# Arduino_FPGA_Design.net
KiCad netlist of a schematic drawn in Altium Designer
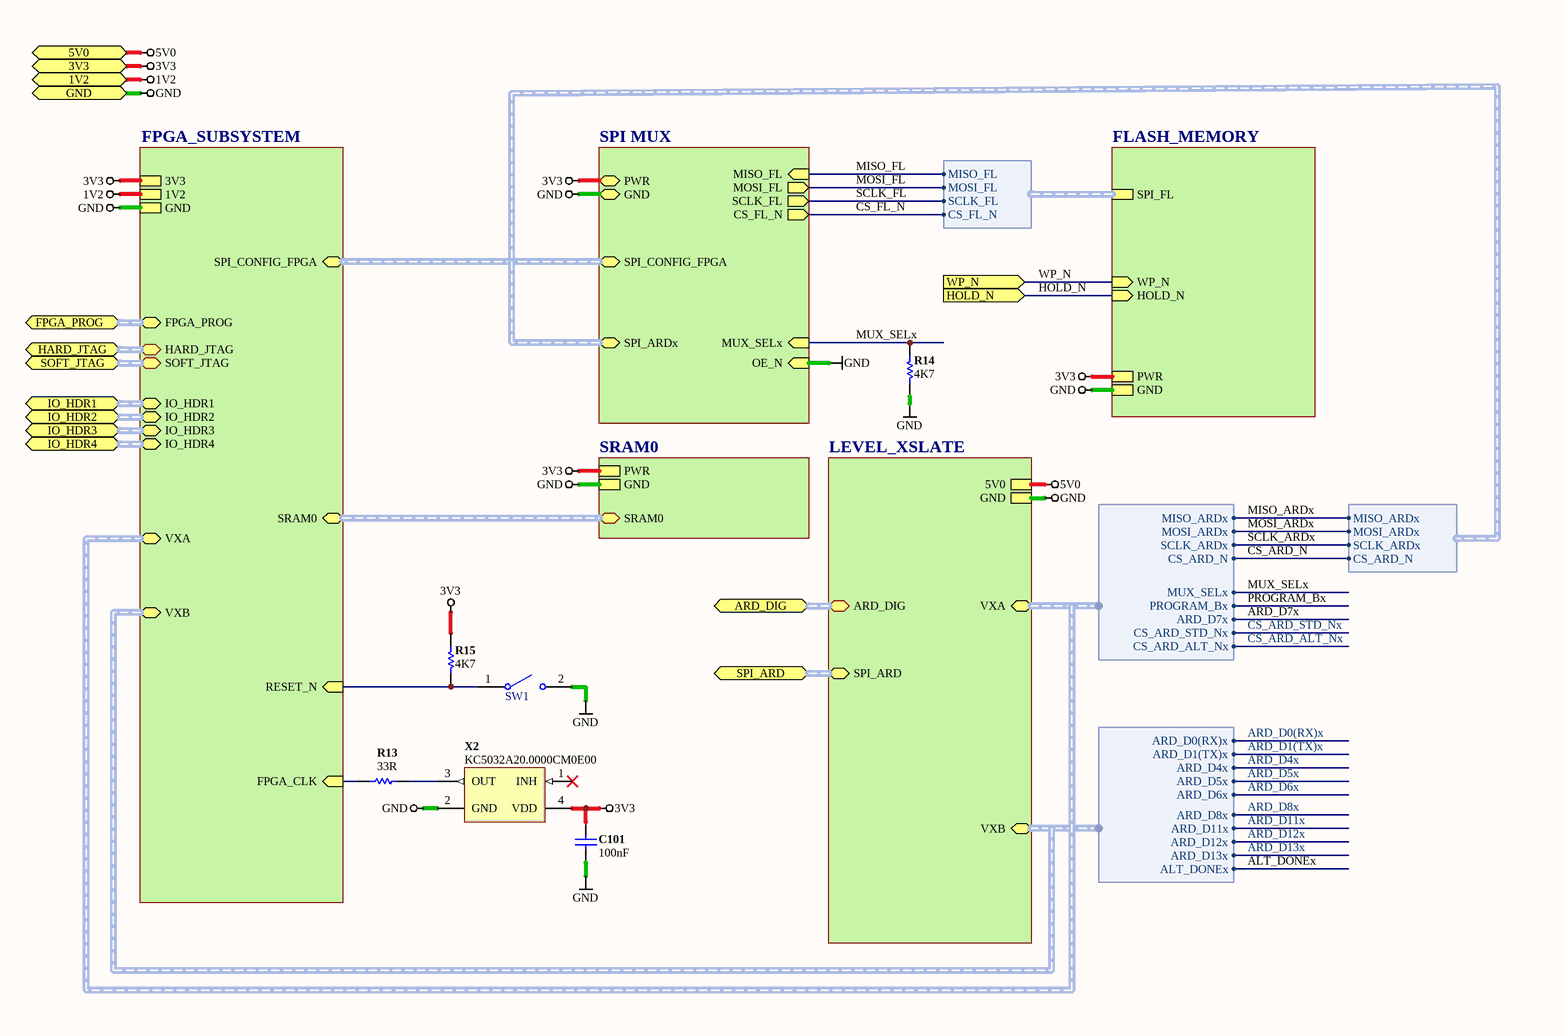
[diagram p0: Arduino FPGA Design.SchDoc]

(export (version "E")
  (design (tool "Eeschema 10.0.6"))
  (components
    (comp (ref "C101")
      (value "100nF")
      (footprint "CAPC0402(1005)60_L")
      (fields
        (field (name "TOLERANCE") "±10%")
        (field (name "MANUFACTURER PART NUMBER") "C0402C104K8PACTU")
        (field (name "Comment") "CAP 100nF 16V 0402(1005)")
      )
      (libsource (lib "Component_Database") (part "CAP_NP"))
    )
    (comp (ref "R13")
      (value "33R")
      (footprint "RESC0402(1005)40_L")
      (fields
        (field (name "POWER") "1/16 W")
        (field (name "MANUFACTURER PART NUMBER") "RC1005F330CS")
        (field (name "Comment") "33R 1 0402")
      )
      (libsource (lib "Component_Database") (part "RES"))
    )
    (comp (ref "R14")
      (value "4K7")
      (footprint "RESC0402(1005)40_L")
      (fields
        (field (name "POWER") "1/16 W")
        (field (name "MANUFACTURER PART NUMBER") "CR0402-FX-4701GLFDKR-ND")
        (field (name "Comment") "4K7 1 0402")
      )
      (libsource (lib "Component_Database") (part "RES"))
    )
    (comp (ref "R15")
      (value "4K7")
      (footprint "RESC0402(1005)40_L")
      (fields
        (field (name "POWER") "1/16 W")
        (field (name "MANUFACTURER PART NUMBER") "CR0402-FX-4701GLFDKR-ND")
        (field (name "Comment") "4K7 1 0402")
      )
      (libsource (lib "Component_Database") (part "RES"))
    )
    (comp (ref "SW1")
      (value "ADTSM32RVTR")
      (footprint "ADTSM32RVTR")
      (description "ADTSM32RVTR SWITCH, TACTILE, SPST-NO, 50mA, 12VDC SMD")
      (fields (field (name "MANUFACTURER") "APEM"))
      (libsource (lib "ADTSM32RVTR") (part "ADTSM32RVTR"))
    )
    (comp (ref "X2")
      (value "KC5032A20.0000CM0E00")
      (footprint "HOSC-L500HW320H105-4_2")
      (fields (field (name "PARTNUMBER") "HCX-C2-20M"))
      (libsource (lib "Component_Database") (part "OSC-4"))
    )
  )
  (nets
    (net (code "30") (name "/FPGA_CLK") (class "Default")
      (node (ref "R13") (pin "1") (pinfunction "1_1") (pintype "passive"))
    )
    (net (code "42") (name "/MUX_SELx") (class "Default")
      (node (ref "R14") (pin "2") (pinfunction "2_2") (pintype "passive"))
    )
    (net (code "44") (name "/RESET_N") (class "Default")
      (node (ref "R15") (pin "1") (pinfunction "1_1") (pintype "passive"))
      (node (ref "SW1") (pin "1") (pinfunction "1_1") (pintype "passive"))
    )
    (net (code "59") (name "3V3") (class "Default")
      (node (ref "C101") (pin "1") (pinfunction "1_1") (pintype "passive"))
      (node (ref "R15") (pin "2") (pinfunction "2_2") (pintype "passive"))
      (node (ref "X2") (pin "4") (pinfunction "VDD_4") (pintype "power_in"))
    )
    (net (code "61") (name "GND") (class "Default")
      (node (ref "C101") (pin "2") (pinfunction "2_2") (pintype "passive"))
      (node (ref "R14") (pin "1") (pinfunction "1_1") (pintype "passive"))
      (node (ref "SW1") (pin "2") (pinfunction "2_2") (pintype "passive"))
      (node (ref "X2") (pin "2") (pinfunction "GND_2") (pintype "power_in"))
    )
    (net (code "62") (name "Net-(X2-OUT)") (class "Default")
      (node (ref "R13") (pin "2") (pinfunction "2_2") (pintype "passive"))
      (node (ref "X2") (pin "3") (pinfunction "OUT_3") (pintype "output"))
    )
    (net (code "63") (name "unconnected-(X2-INH-Pad1)") (class "Default")
      (node (ref "X2") (pin "1") (pinfunction "INH_1") (pintype "input+no_connect"))
    )
  )
)
